# mp28164-buck-boost-flashlight-driver-17m.net
KiCad netlist of a schematic drawn in EAGLE
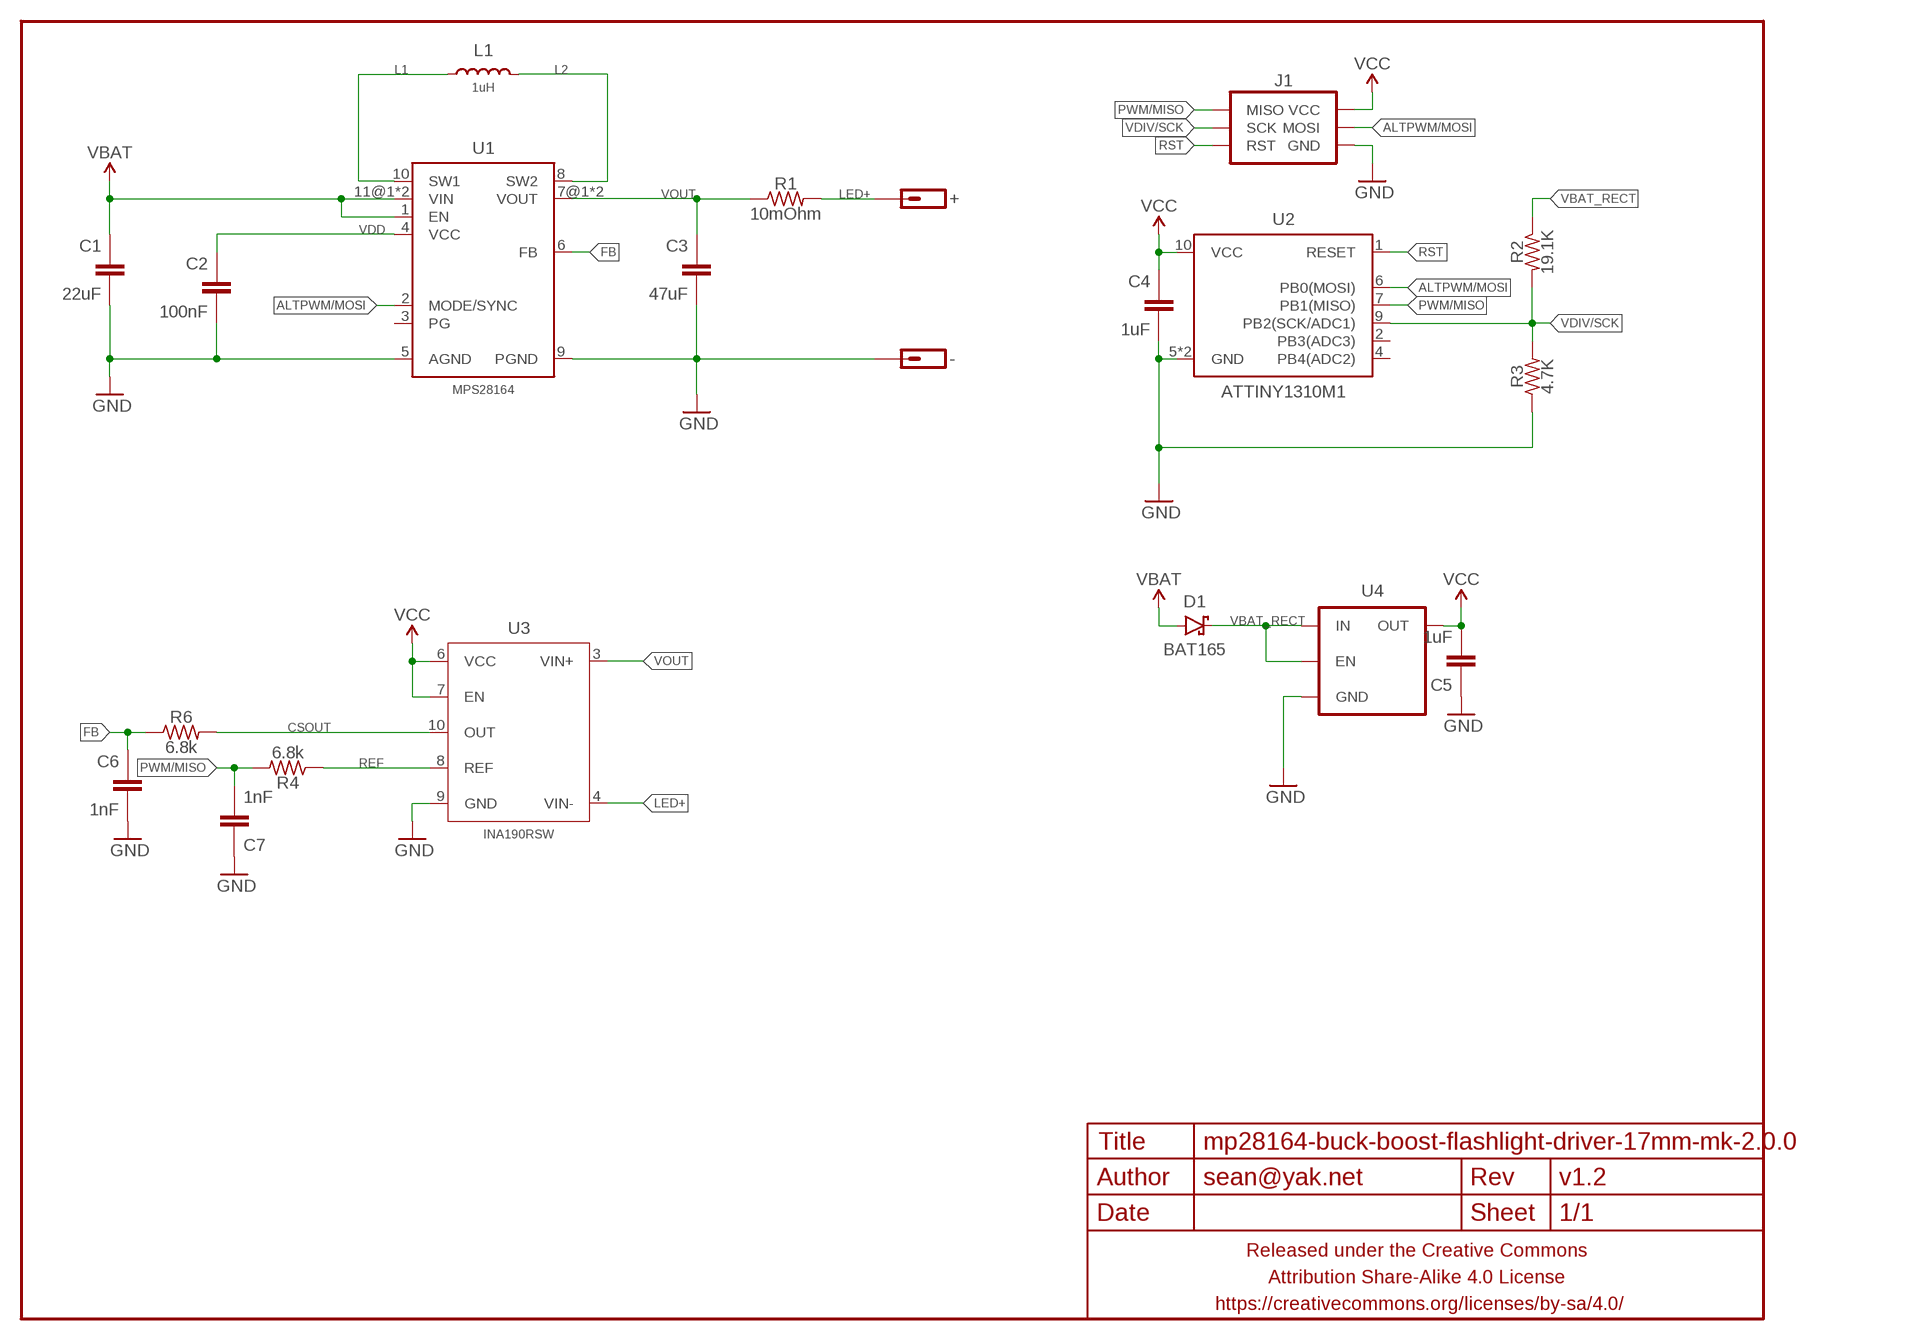
[diagram p0: schematic, sheet 1]

(export (version "E")
  (design (tool "Eeschema 10.0.6"))
  (components
    (comp (ref "+")
      (value "M01SMD-1.6MMX3.2MM-NS")
      (footprint "eagle-import:1X01-SMD-1.6MMX3.2MM-NS")
      (libsource (lib "eagle-import") (part "M01SMD-1.6MMX3.2MM-NS"))
    )
    (comp (ref "-")
      (value "M01SMD-1.6MMX3.2MM-NS")
      (footprint "eagle-import:1X01-SMD-1.6MMX3.2MM-NS")
      (libsource (lib "eagle-import") (part "M01SMD-1.6MMX3.2MM-NS"))
    )
    (comp (ref "C1")
      (value "22uF")
      (footprint "eagle-import:C1206")
      (libsource (lib "eagle-import") (part "CAPACITOR-CERAMICC1206"))
    )
    (comp (ref "C2")
      (value "100nF")
      (footprint "eagle-import:C0402")
      (libsource (lib "eagle-import") (part "CAPACITOR-CERAMICC0402"))
    )
    (comp (ref "C3")
      (value "47uF")
      (footprint "eagle-import:C1206")
      (libsource (lib "eagle-import") (part "CAPACITOR-CERAMICC1206"))
    )
    (comp (ref "C4")
      (value "1uF")
      (footprint "eagle-import:C0402")
      (libsource (lib "eagle-import") (part "CAPACITOR-CERAMICC0402"))
    )
    (comp (ref "C5")
      (value "1uF")
      (footprint "eagle-import:C0402")
      (libsource (lib "eagle-import") (part "CAPACITOR-CERAMICC0402"))
    )
    (comp (ref "C6")
      (value "1nF")
      (footprint "eagle-import:C0402")
      (libsource (lib "eagle-import") (part "CAPACITOR-CERAMICC0402"))
    )
    (comp (ref "C7")
      (value "1nF")
      (footprint "eagle-import:C0402")
      (libsource (lib "eagle-import") (part "CAPACITOR-CERAMICC0402"))
    )
    (comp (ref "D1")
      (value "BAT165")
      (footprint "eagle-import:SOD323-SCHOTTKY")
      (libsource (lib "eagle-import") (part "DIODE-SCHOTTKYSOD323"))
    )
    (comp (ref "FRAME1")
      (value "FRAME-LETTERNO_PACKAGE")
      (footprint "eagle-import:DUMMY")
      (fields
        (field (name "DESIGNER") "sean@yak.net")
        (field (name "VERSION") "v1.2")
        (field (name "DESIGNER_1") "sean@yak.net")
        (field (name "VERSION_1") "v1.2")
      )
      (libsource (lib "eagle-import") (part "FRAME-LETTERNO_PACKAGE"))
    )
    (comp (ref "J1")
      (value "AVR_SPI_PRG_6SMD-1.27MM")
      (footprint "eagle-import:2X3-1.27MM-SMD")
      (libsource (lib "eagle-import") (part "AVR_SPI_PRG_6SMD-1.27MM"))
    )
    (comp (ref "L1")
      (value "1uH")
      (footprint "eagle-import:XAL60XX")
      (libsource (lib "eagle-import") (part "INDUCTORXAL60XX"))
    )
    (comp (ref "R1")
      (value "10mOhm")
      (footprint "eagle-import:R1206")
      (libsource (lib "eagle-import") (part "RESISTORR1206"))
    )
    (comp (ref "R2")
      (value "19.1K")
      (footprint "eagle-import:R0402")
      (libsource (lib "eagle-import") (part "RESISTORR0402"))
    )
    (comp (ref "R3")
      (value "4.7K")
      (footprint "eagle-import:R0402")
      (libsource (lib "eagle-import") (part "RESISTORR0402"))
    )
    (comp (ref "R4")
      (value "6.8k")
      (footprint "eagle-import:R0402")
      (libsource (lib "eagle-import") (part "RESISTORR0402"))
    )
    (comp (ref "R6")
      (value "6.8k")
      (footprint "eagle-import:R0402")
      (libsource (lib "eagle-import") (part "RESISTORR0402"))
    )
    (comp (ref "U1")
      (value "MPS28164")
      (footprint "eagle-import:MPS28164")
      (libsource (lib "eagle-import") (part "MPS28164"))
    )
    (comp (ref "U2")
      (value "ATTINY1310M1")
      (footprint "eagle-import:QFN10(2X5)")
      (libsource (lib "eagle-import") (part "ATTINY1310M1"))
    )
    (comp (ref "U3")
      (value "INA190RSW")
      (footprint "eagle-import:UQFN-10")
      (libsource (lib "eagle-import") (part "INA190RSW"))
    )
    (comp (ref "U4")
      (value "V_REG_ENTLV700")
      (footprint "eagle-import:SC70")
      (libsource (lib "eagle-import") (part "V_REG_ENTLV700"))
    )
  )
  (nets
    (net (code "1") (name "/CSOUT") (class "Default")
      (node (ref "R6") (pin "2") (pinfunction "2_2") (pintype "passive"))
      (node (ref "U3") (pin "10") (pinfunction "OUT_10") (pintype "bidirectional"))
    )
    (net (code "2") (name "/L1") (class "Default")
      (node (ref "L1") (pin "P$1") (pinfunction "1_P$1") (pintype "passive"))
      (node (ref "U1") (pin "10") (pinfunction "SW1_10") (pintype "bidirectional"))
    )
    (net (code "3") (name "/L2") (class "Default")
      (node (ref "L1") (pin "P$2") (pinfunction "2_P$2") (pintype "passive"))
      (node (ref "U1") (pin "8") (pinfunction "SW2_8") (pintype "bidirectional"))
    )
    (net (code "4") (name "/REF") (class "Default")
      (node (ref "R4") (pin "1") (pinfunction "1_1") (pintype "passive"))
      (node (ref "U3") (pin "8") (pinfunction "REF_8") (pintype "bidirectional"))
    )
    (net (code "5") (name "/VDD") (class "Default")
      (node (ref "C2") (pin "1") (pinfunction "1_1") (pintype "passive"))
      (node (ref "U1") (pin "4") (pinfunction "VCC_4") (pintype "bidirectional"))
    )
    (net (code "6") (name "ALTPWM{slash}MOSI") (class "Default")
      (node (ref "J1") (pin "4") (pinfunction "MOSI_4") (pintype "passive"))
      (node (ref "U1") (pin "2") (pinfunction "MODE/SYNC_2") (pintype "bidirectional"))
      (node (ref "U2") (pin "6") (pinfunction "PB0(MOSI)_6") (pintype "bidirectional"))
    )
    (net (code "7") (name "FB") (class "Default")
      (node (ref "C6") (pin "1") (pinfunction "1_1") (pintype "passive"))
      (node (ref "R6") (pin "1") (pinfunction "1_1") (pintype "passive"))
      (node (ref "U1") (pin "6") (pinfunction "FB_6") (pintype "bidirectional"))
    )
    (net (code "8") (name "GND") (class "Default")
      (node (ref "-") (pin "P$1") (pinfunction "1_P$1") (pintype "passive"))
      (node (ref "C1") (pin "2") (pinfunction "2_2") (pintype "passive"))
      (node (ref "C2") (pin "2") (pinfunction "2_2") (pintype "passive"))
      (node (ref "C3") (pin "2") (pinfunction "2_2") (pintype "passive"))
      (node (ref "C4") (pin "2") (pinfunction "2_2") (pintype "passive"))
      (node (ref "C5") (pin "1") (pinfunction "1_1") (pintype "passive"))
      (node (ref "C6") (pin "2") (pinfunction "2_2") (pintype "passive"))
      (node (ref "C7") (pin "1") (pinfunction "1_1") (pintype "passive"))
      (node (ref "J1") (pin "6") (pinfunction "GND_6") (pintype "passive"))
      (node (ref "R3") (pin "1") (pinfunction "1_1") (pintype "passive"))
      (node (ref "U1") (pin "5") (pinfunction "AGND_5") (pintype "bidirectional"))
      (node (ref "U1") (pin "9") (pinfunction "PGND_9") (pintype "bidirectional"))
      (node (ref "U2") (pin "5") (pinfunction "GND_5") (pintype "bidirectional"))
      (node (ref "U2") (pin "PAD") (pinfunction "GND_PAD") (pintype "bidirectional"))
      (node (ref "U3") (pin "9") (pinfunction "GND_9") (pintype "bidirectional"))
      (node (ref "U4") (pin "2") (pinfunction "GND_2") (pintype "input"))
    )
    (net (code "9") (name "LED+") (class "Default")
      (node (ref "+") (pin "P$1") (pinfunction "1_P$1") (pintype "passive"))
      (node (ref "R1") (pin "2") (pinfunction "2_2") (pintype "passive"))
      (node (ref "U3") (pin "4") (pinfunction "VIN-_4") (pintype "bidirectional"))
    )
    (net (code "10") (name "PWM{slash}MISO") (class "Default")
      (node (ref "C7") (pin "2") (pinfunction "2_2") (pintype "passive"))
      (node (ref "J1") (pin "1") (pinfunction "MISO_1") (pintype "passive"))
      (node (ref "R4") (pin "2") (pinfunction "2_2") (pintype "passive"))
      (node (ref "U2") (pin "7") (pinfunction "PB1(MISO)_7") (pintype "bidirectional"))
    )
    (net (code "11") (name "RST") (class "Default")
      (node (ref "J1") (pin "5") (pinfunction "RST_5") (pintype "passive"))
      (node (ref "U2") (pin "1") (pinfunction "RESET_1") (pintype "bidirectional"))
    )
    (net (code "12") (name "VBAT") (class "Default")
      (node (ref "C1") (pin "1") (pinfunction "1_1") (pintype "passive"))
      (node (ref "D1") (pin "A") (pinfunction "A_A") (pintype "passive"))
      (node (ref "U1") (pin "1") (pinfunction "EN_1") (pintype "bidirectional"))
      (node (ref "U1") (pin "11@1") (pinfunction "VIN_11@1") (pintype "bidirectional"))
      (node (ref "U1") (pin "11@2") (pinfunction "VIN_11@2") (pintype "bidirectional"))
    )
    (net (code "13") (name "VBAT_RECT") (class "Default")
      (node (ref "D1") (pin "C") (pinfunction "C_C") (pintype "passive"))
      (node (ref "R2") (pin "1") (pinfunction "1_1") (pintype "passive"))
      (node (ref "U4") (pin "1") (pinfunction "IN_1") (pintype "input"))
      (node (ref "U4") (pin "3") (pinfunction "EN_3") (pintype "input"))
    )
    (net (code "14") (name "VCC") (class "Default")
      (node (ref "C4") (pin "1") (pinfunction "1_1") (pintype "passive"))
      (node (ref "C5") (pin "2") (pinfunction "2_2") (pintype "passive"))
      (node (ref "J1") (pin "2") (pinfunction "VCC_2") (pintype "passive"))
      (node (ref "U2") (pin "10") (pinfunction "VCC_10") (pintype "bidirectional"))
      (node (ref "U3") (pin "6") (pinfunction "VCC_6") (pintype "bidirectional"))
      (node (ref "U3") (pin "7") (pinfunction "EN_7") (pintype "bidirectional"))
      (node (ref "U4") (pin "5") (pinfunction "OUT_5") (pintype "passive"))
    )
    (net (code "15") (name "VDIV{slash}SCK") (class "Default")
      (node (ref "J1") (pin "3") (pinfunction "SCK_3") (pintype "passive"))
      (node (ref "R2") (pin "2") (pinfunction "2_2") (pintype "passive"))
      (node (ref "R3") (pin "2") (pinfunction "2_2") (pintype "passive"))
      (node (ref "U2") (pin "9") (pinfunction "PB2(SCK/ADC1)_9") (pintype "bidirectional"))
    )
    (net (code "16") (name "VOUT") (class "Default")
      (node (ref "C3") (pin "1") (pinfunction "1_1") (pintype "passive"))
      (node (ref "R1") (pin "1") (pinfunction "1_1") (pintype "passive"))
      (node (ref "U1") (pin "7@1") (pinfunction "VOUT_7@1") (pintype "bidirectional"))
      (node (ref "U1") (pin "7@2") (pinfunction "VOUT_7@2") (pintype "bidirectional"))
      (node (ref "U3") (pin "3") (pinfunction "VIN+_3") (pintype "bidirectional"))
    )
    (net (code "17") (name "unconnected-(U1-PG-Pad3)") (class "Default")
      (node (ref "U1") (pin "3") (pinfunction "PG_3") (pintype "bidirectional"))
    )
    (net (code "18") (name "unconnected-(U2-PB3(ADC3)-Pad2)") (class "Default")
      (node (ref "U2") (pin "2") (pinfunction "PB3(ADC3)_2") (pintype "bidirectional"))
    )
    (net (code "19") (name "unconnected-(U2-PB4(ADC2)-Pad4)") (class "Default")
      (node (ref "U2") (pin "4") (pinfunction "PB4(ADC2)_4") (pintype "bidirectional"))
    )
  )
)
